# MPPT_power.net
KiCad netlist of a schematic drawn in EAGLE
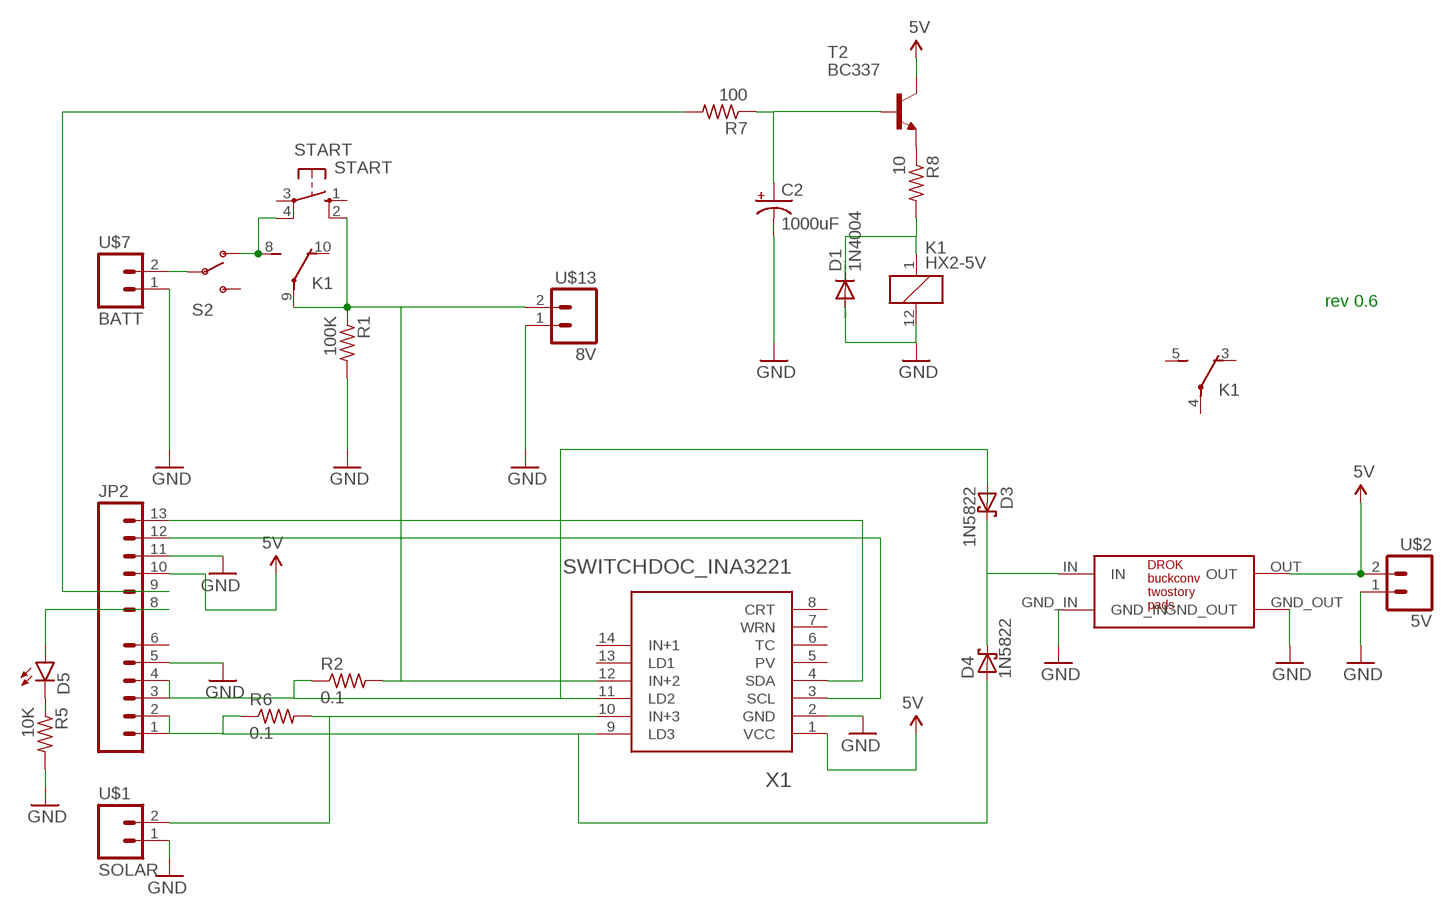
[diagram p0: schematic, sheet 1]

(export (version "E")
  (design (tool "Eeschema 10.0.6"))
  (components
    (comp (ref "C2")
      (value "1000uF")
      (footprint "eagle-import:CPOL-RADIAL-1000UF-25V")
      (libsource (lib "eagle-import") (part "1000UF-25V(PTH)"))
    )
    (comp (ref "D1")
      (value "1N4004")
      (footprint "eagle-import:DO41-10")
      (libsource (lib "eagle-import") (part "1N4004"))
    )
    (comp (ref "D3")
      (value "1N5822")
      (footprint "eagle-import:DO201T15")
      (libsource (lib "eagle-import") (part "1N5822"))
    )
    (comp (ref "D4")
      (value "1N5822")
      (footprint "eagle-import:DO201T15")
      (libsource (lib "eagle-import") (part "1N5822"))
    )
    (comp (ref "D5")
      (value "LED5MM")
      (footprint "eagle-import:LED5MM")
      (libsource (lib "eagle-import") (part "LED5MM"))
    )
    (comp (ref "JP2")
      (value "M06_PLUS_06MPPT")
      (footprint "eagle-import:M06_PLUS_06_MPPT")
      (libsource (lib "eagle-import") (part "M06_PLUS_06MPPT"))
    )
    (comp (ref "K1")
      (value "HX2-5V")
      (footprint "eagle-import:HX")
      (libsource (lib "eagle-import") (part "HX2-5V"))
    )
    (comp (ref "R1")
      (value "100K")
      (footprint "eagle-import:0204_7")
      (libsource (lib "eagle-import") (part "R-US_0204/7"))
    )
    (comp (ref "R2")
      (value "0.1")
      (footprint "eagle-import:0204_7_PHAT_PAD")
      (libsource (lib "eagle-import") (part "R-US_"))
    )
    (comp (ref "R5")
      (value "10K")
      (footprint "eagle-import:0204_7")
      (libsource (lib "eagle-import") (part "R-US_0204/7"))
    )
    (comp (ref "R6")
      (value "0.1")
      (footprint "eagle-import:0204_7_PHAT_PAD")
      (libsource (lib "eagle-import") (part "R-US_"))
    )
    (comp (ref "R7")
      (value "100")
      (footprint "eagle-import:0204_7")
      (libsource (lib "eagle-import") (part "R-US_0204/7"))
    )
    (comp (ref "R8")
      (value "10")
      (footprint "eagle-import:0204_7")
      (libsource (lib "eagle-import") (part "R-US_0204/7"))
    )
    (comp (ref "S2")
      (value "SWITCH-SPDT")
      (footprint "eagle-import:SWITCH-SPDT_0.15_INCH")
      (libsource (lib "eagle-import") (part "SWITCH-SPDT"))
    )
    (comp (ref "START")
      (value "START")
      (footprint "eagle-import:B3F-10XX")
      (libsource (lib "eagle-import") (part "10-XX"))
    )
    (comp (ref "T2")
      (value "BC337")
      (footprint "eagle-import:TO92")
      (libsource (lib "eagle-import") (part "BC337"))
    )
    (comp (ref "U$1")
      (value "SOLAR")
      (footprint "eagle-import:W237-132")
      (libsource (lib "eagle-import") (part "SCREW_TERMINAL"))
    )
    (comp (ref "U$2")
      (value "5V")
      (footprint "eagle-import:W237-132")
      (libsource (lib "eagle-import") (part "SCREW_TERMINAL"))
    )
    (comp (ref "U$3")
      (value "DROK_BUCKCONV_TWOSTORY_PADS")
      (footprint "eagle-import:DROK_BUCKCONV_TWOSTORY_PADS")
      (libsource (lib "eagle-import") (part "DROK_BUCKCONV_TWOSTORY_PADS"))
    )
    (comp (ref "U$7")
      (value "BATT")
      (footprint "eagle-import:W237-132")
      (libsource (lib "eagle-import") (part "SCREW_TERMINAL"))
    )
    (comp (ref "U$13")
      (value "8V")
      (footprint "eagle-import:W237-132")
      (libsource (lib "eagle-import") (part "SCREW_TERMINAL"))
    )
    (comp (ref "X1")
      (value "SWITCHDOC_INA3221")
      (footprint "eagle-import:SWITCHDOC_INA3221_NODRILL")
      (libsource (lib "eagle-import") (part "SWITCHDOC_INA3221"))
    )
  )
  (nets
    (net (code "1") (name "5V") (class "Default")
      (node (ref "JP2") (pin "10") (pinfunction "10_10") (pintype "passive"))
      (node (ref "T2") (pin "3") (pinfunction "C_3") (pintype "passive"))
      (node (ref "U$2") (pin "2") (pinfunction "2_2") (pintype "passive"))
      (node (ref "U$3") (pin "OUT") (pinfunction "OUT_OUT") (pintype "bidirectional"))
      (node (ref "X1") (pin "1") (pinfunction "VCC_1") (pintype "power_in"))
    )
    (net (code "2") (name "GND") (class "Default")
      (node (ref "C2") (pin "-") (pinfunction "-_-") (pintype "passive"))
      (node (ref "D1") (pin "A") (pinfunction "A_A") (pintype "passive"))
      (node (ref "JP2") (pin "11") (pinfunction "11_11") (pintype "passive"))
      (node (ref "JP2") (pin "5") (pinfunction "5_5") (pintype "passive"))
      (node (ref "K1") (pin "12") (pinfunction "2_12") (pintype "passive"))
      (node (ref "R1") (pin "2") (pinfunction "2_2") (pintype "passive"))
      (node (ref "R5") (pin "2") (pinfunction "2_2") (pintype "passive"))
      (node (ref "U$1") (pin "1") (pinfunction "1_1") (pintype "passive"))
      (node (ref "U$13") (pin "1") (pinfunction "1_1") (pintype "passive"))
      (node (ref "U$2") (pin "1") (pinfunction "1_1") (pintype "passive"))
      (node (ref "U$3") (pin "GND_IN") (pinfunction "GND_IN_GND_IN") (pintype "bidirectional"))
      (node (ref "U$3") (pin "GND_OUT") (pinfunction "GND_OUT_GND_OUT") (pintype "bidirectional"))
      (node (ref "U$7") (pin "1") (pinfunction "1_1") (pintype "passive"))
      (node (ref "X1") (pin "2") (pinfunction "GND_2") (pintype "power_in"))
    )
    (net (code "3") (name "Net-(D1-PadC)") (class "Default")
      (node (ref "D1") (pin "C") (pinfunction "C_C") (pintype "passive"))
      (node (ref "K1") (pin "1") (pinfunction "1_1") (pintype "passive"))
      (node (ref "R8") (pin "2") (pinfunction "2_2") (pintype "passive"))
    )
    (net (code "4") (name "Net-(D3-PadC)") (class "Default")
      (node (ref "D3") (pin "C") (pinfunction "C_C") (pintype "passive"))
      (node (ref "D4") (pin "C") (pinfunction "C_C") (pintype "passive"))
      (node (ref "U$3") (pin "IN") (pinfunction "IN_IN") (pintype "bidirectional"))
    )
    (net (code "5") (name "Net-(D5-C)") (class "Default")
      (node (ref "D5") (pin "K") (pinfunction "C_K") (pintype "passive"))
      (node (ref "R5") (pin "1") (pinfunction "1_1") (pintype "passive"))
    )
    (net (code "6") (name "Net-(D5-PadA)") (class "Default")
      (node (ref "D5") (pin "A") (pinfunction "A_A") (pintype "passive"))
      (node (ref "JP2") (pin "8") (pinfunction "8_8") (pintype "passive"))
    )
    (net (code "7") (name "Net-(JP2-Pad9)") (class "Default")
      (node (ref "JP2") (pin "9") (pinfunction "9_9") (pintype "passive"))
      (node (ref "R7") (pin "2") (pinfunction "2_2") (pintype "passive"))
    )
    (net (code "8") (name "Net-(K1C-P)") (class "Default")
      (node (ref "K1") (pin "9") (pinfunction "P_9") (pintype "passive"))
      (node (ref "R1") (pin "1") (pinfunction "1_1") (pintype "passive"))
      (node (ref "R2") (pin "2") (pinfunction "2_2") (pintype "passive"))
      (node (ref "START") (pin "2") (pinfunction "S1_2") (pintype "passive"))
      (node (ref "U$13") (pin "2") (pinfunction "2_2") (pintype "passive"))
      (node (ref "X1") (pin "12") (pinfunction "IN+2_12") (pintype "bidirectional"))
    )
    (net (code "9") (name "Net-(K1C-S)") (class "Default")
      (node (ref "K1") (pin "8") (pinfunction "S_8") (pintype "passive"))
      (node (ref "S2") (pin "1") (pinfunction "O_1") (pintype "passive"))
      (node (ref "START") (pin "4") (pinfunction "P1_4") (pintype "passive"))
    )
    (net (code "10") (name "Net-(S2-P)") (class "Default")
      (node (ref "S2") (pin "2") (pinfunction "P_2") (pintype "passive"))
      (node (ref "U$7") (pin "2") (pinfunction "2_2") (pintype "passive"))
    )
    (net (code "11") (name "Net-(T2-B)") (class "Default")
      (node (ref "C2") (pin "+") (pinfunction "+_+") (pintype "passive"))
      (node (ref "R7") (pin "1") (pinfunction "1_1") (pintype "passive"))
      (node (ref "T2") (pin "2") (pinfunction "B_2") (pintype "passive"))
    )
    (net (code "12") (name "Net-(T2-E)") (class "Default")
      (node (ref "R8") (pin "1") (pinfunction "1_1") (pintype "passive"))
      (node (ref "T2") (pin "1") (pinfunction "E_1") (pintype "passive"))
    )
    (net (code "13") (name "Net-(X1-IN+3)") (class "Default")
      (node (ref "R6") (pin "2") (pinfunction "2_2") (pintype "passive"))
      (node (ref "U$1") (pin "2") (pinfunction "2_2") (pintype "passive"))
      (node (ref "X1") (pin "10") (pinfunction "IN+3_10") (pintype "bidirectional"))
    )
    (net (code "14") (name "Net-(X1-LD2)") (class "Default")
      (node (ref "D3") (pin "A") (pinfunction "A_A") (pintype "passive"))
      (node (ref "JP2") (pin "3") (pinfunction "3_3") (pintype "passive"))
      (node (ref "JP2") (pin "4") (pinfunction "4_4") (pintype "passive"))
      (node (ref "R2") (pin "1") (pinfunction "1_1") (pintype "passive"))
      (node (ref "X1") (pin "11") (pinfunction "LD2_11") (pintype "bidirectional"))
    )
    (net (code "15") (name "Net-(X1-LD3)") (class "Default")
      (node (ref "D4") (pin "A") (pinfunction "A_A") (pintype "passive"))
      (node (ref "JP2") (pin "1") (pinfunction "1_1") (pintype "passive"))
      (node (ref "JP2") (pin "2") (pinfunction "2_2") (pintype "passive"))
      (node (ref "R6") (pin "1") (pinfunction "1_1") (pintype "passive"))
      (node (ref "X1") (pin "9") (pinfunction "LD3_9") (pintype "bidirectional"))
    )
    (net (code "16") (name "Net-(X1-SCL)") (class "Default")
      (node (ref "JP2") (pin "12") (pinfunction "12_12") (pintype "passive"))
      (node (ref "X1") (pin "3") (pinfunction "SCL_3") (pintype "input"))
    )
    (net (code "17") (name "Net-(X1-SDA)") (class "Default")
      (node (ref "JP2") (pin "13") (pinfunction "13_13") (pintype "passive"))
      (node (ref "X1") (pin "4") (pinfunction "SDA_4") (pintype "input"))
    )
    (net (code "18") (name "unconnected-(JP2-Pad6)") (class "Default")
      (node (ref "JP2") (pin "6") (pinfunction "6_6") (pintype "passive"))
    )
    (net (code "19") (name "unconnected-(K1B-O-Pad3)") (class "Default")
      (node (ref "K1") (pin "3") (pinfunction "O_3") (pintype "passive"))
    )
    (net (code "20") (name "unconnected-(K1B-P-Pad4)") (class "Default")
      (node (ref "K1") (pin "4") (pinfunction "P_4") (pintype "passive"))
    )
    (net (code "21") (name "unconnected-(K1B-S-Pad5)") (class "Default")
      (node (ref "K1") (pin "5") (pinfunction "S_5") (pintype "passive"))
    )
    (net (code "22") (name "unconnected-(K1C-O-Pad10)") (class "Default")
      (node (ref "K1") (pin "10") (pinfunction "O_10") (pintype "passive"))
    )
    (net (code "23") (name "unconnected-(S2-S-Pad3)") (class "Default")
      (node (ref "S2") (pin "3") (pinfunction "S_3") (pintype "passive"))
    )
    (net (code "24") (name "unconnected-(START-P-Pad3)") (class "Default")
      (node (ref "START") (pin "3") (pinfunction "P_3") (pintype "passive"))
    )
    (net (code "25") (name "unconnected-(START-S-Pad1)") (class "Default")
      (node (ref "START") (pin "1") (pinfunction "S_1") (pintype "passive"))
    )
    (net (code "26") (name "unconnected-(X1-CRT-Pad8)") (class "Default")
      (node (ref "X1") (pin "8") (pinfunction "CRT_8") (pintype "bidirectional"))
    )
    (net (code "27") (name "unconnected-(X1-IN+1-Pad14)") (class "Default")
      (node (ref "X1") (pin "14") (pinfunction "IN+1_14") (pintype "bidirectional"))
    )
    (net (code "28") (name "unconnected-(X1-LD1-Pad13)") (class "Default")
      (node (ref "X1") (pin "13") (pinfunction "LD1_13") (pintype "bidirectional"))
    )
    (net (code "29") (name "unconnected-(X1-PV-Pad5)") (class "Default")
      (node (ref "X1") (pin "5") (pinfunction "PV_5") (pintype "input"))
    )
    (net (code "30") (name "unconnected-(X1-TC-Pad6)") (class "Default")
      (node (ref "X1") (pin "6") (pinfunction "TC_6") (pintype "input"))
    )
    (net (code "31") (name "unconnected-(X1-WRN-Pad7)") (class "Default")
      (node (ref "X1") (pin "7") (pinfunction "WRN_7") (pintype "bidirectional"))
    )
  )
)
